# Main_board.net
KiCad netlist of a schematic drawn in EAGLE
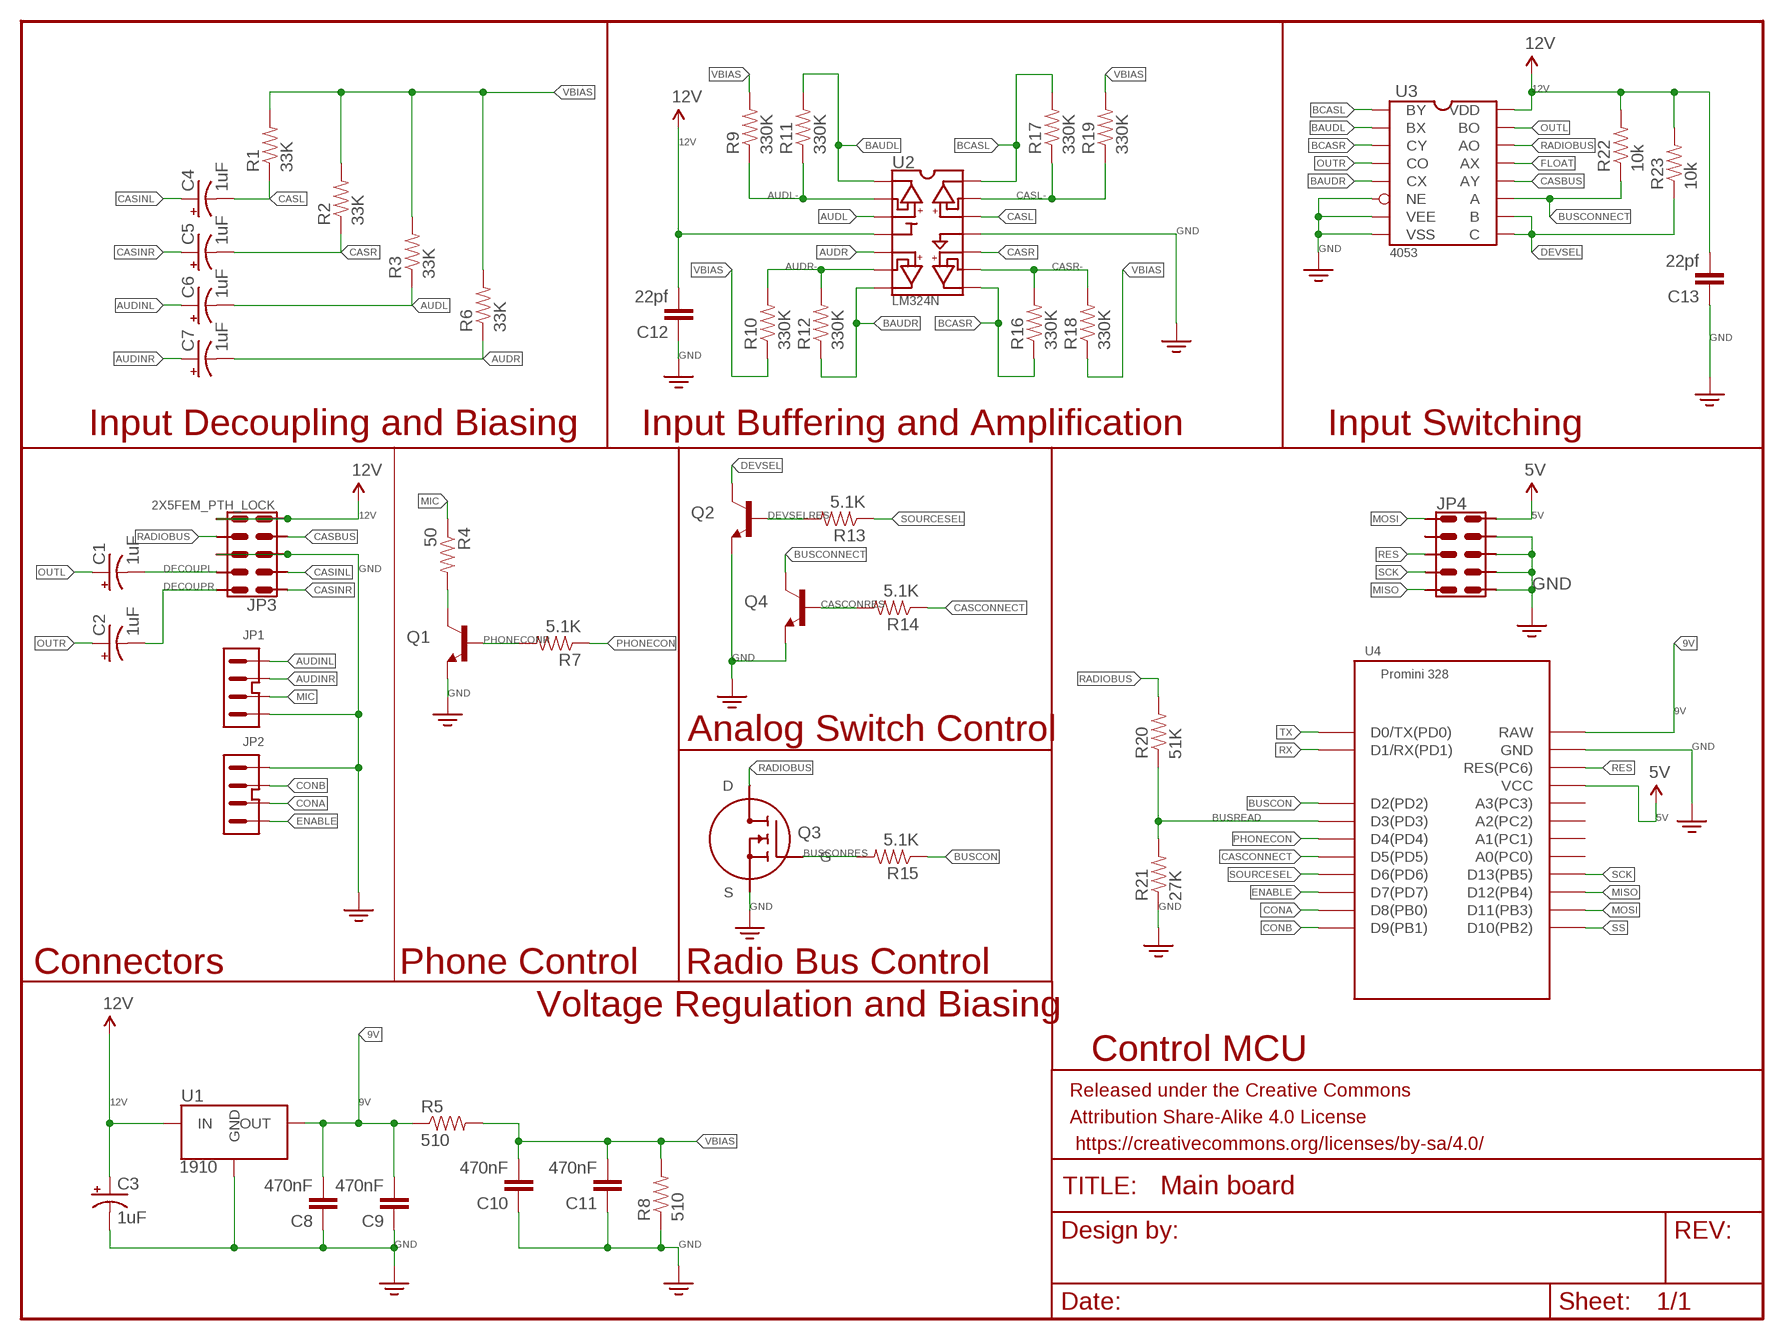
[diagram p0: schematic, sheet 1]

(export (version "E")
  (design (tool "Eeschema 10.0.6"))
  (components
    (comp (ref "C1")
      (value "1uF")
      (footprint "eagle-import:CPOL-RADIAL-10UF-25V")
      (libsource (lib "eagle-import") (part "CAP_POLPTH2"))
    )
    (comp (ref "C2")
      (value "1uF")
      (footprint "eagle-import:CPOL-RADIAL-10UF-25V")
      (libsource (lib "eagle-import") (part "CAP_POLPTH2"))
    )
    (comp (ref "C3")
      (value "1uF")
      (footprint "eagle-import:CPOL-RADIAL-10UF-25V")
      (libsource (lib "eagle-import") (part "CAP_POLPTH2"))
    )
    (comp (ref "C4")
      (value "1uF")
      (footprint "eagle-import:CPOL-RADIAL-10UF-25V")
      (libsource (lib "eagle-import") (part "CAP_POLPTH2"))
    )
    (comp (ref "C5")
      (value "1uF")
      (footprint "eagle-import:CPOL-RADIAL-10UF-25V")
      (libsource (lib "eagle-import") (part "CAP_POLPTH2"))
    )
    (comp (ref "C6")
      (value "1uF")
      (footprint "eagle-import:CPOL-RADIAL-10UF-25V")
      (libsource (lib "eagle-import") (part "CAP_POLPTH2"))
    )
    (comp (ref "C7")
      (value "1uF")
      (footprint "eagle-import:CPOL-RADIAL-10UF-25V")
      (libsource (lib "eagle-import") (part "CAP_POLPTH2"))
    )
    (comp (ref "C8")
      (value "470nF")
      (footprint "eagle-import:0603-CAP")
      (libsource (lib "eagle-import") (part "CAP0603-CAP"))
    )
    (comp (ref "C9")
      (value "470nF")
      (footprint "eagle-import:0603-CAP")
      (libsource (lib "eagle-import") (part "CAP0603-CAP"))
    )
    (comp (ref "C10")
      (value "470nF")
      (footprint "eagle-import:0603-CAP")
      (libsource (lib "eagle-import") (part "CAP0603-CAP"))
    )
    (comp (ref "C11")
      (value "470nF")
      (footprint "eagle-import:0603-CAP")
      (libsource (lib "eagle-import") (part "CAP0603-CAP"))
    )
    (comp (ref "C12")
      (value "22pf")
      (footprint "eagle-import:0603-CAP")
      (libsource (lib "eagle-import") (part "CAP0603-CAP"))
    )
    (comp (ref "C13")
      (value "22pf")
      (footprint "eagle-import:0603-CAP")
      (libsource (lib "eagle-import") (part "CAP0603-CAP"))
    )
    (comp (ref "FRAME1")
      (value "FRAME-LETTERNO_PACKAGE")
      (footprint "eagle-import:DUMMY")
      (fields (field (name "DESIGNER") "Nobody"))
      (libsource (lib "eagle-import") (part "FRAME-LETTERNO_PACKAGE"))
    )
    (comp (ref "JP1")
      (value "4PINJST")
      (footprint "eagle-import:JST-4-PTH-VERT")
      (libsource (lib "eagle-import") (part "4PINJST"))
    )
    (comp (ref "JP2")
      (value "4PINJST")
      (footprint "eagle-import:JST-4-PTH-VERT")
      (libsource (lib "eagle-import") (part "4PINJST"))
    )
    (comp (ref "JP3")
      (value "2X5FEM_PTH_LOCK")
      (footprint "eagle-import:2X5PTHFEMLOCK")
      (libsource (lib "eagle-import") (part "2X5FEM_PTH_LOCK"))
    )
    (comp (ref "JP4")
      (value "2X5FEM_PTH_LOCK")
      (footprint "eagle-import:2X5PTHFEMLOCK")
      (libsource (lib "eagle-import") (part "2X5FEM_PTH_LOCK"))
    )
    (comp (ref "Q1")
      (value "TRANSISTOR_NPNTO-92-AMMO")
      (footprint "eagle-import:TO-92-AMMO")
      (libsource (lib "eagle-import") (part "TRANSISTOR_NPNTO-92-AMMO"))
    )
    (comp (ref "Q2")
      (value "TRANSISTOR_NPNTO-92-AMMO")
      (footprint "eagle-import:TO-92-AMMO")
      (libsource (lib "eagle-import") (part "TRANSISTOR_NPNTO-92-AMMO"))
    )
    (comp (ref "Q3")
      (value "BUZ101S")
      (footprint "eagle-import:TO-220")
      (libsource (lib "eagle-import") (part "BUZ101S"))
    )
    (comp (ref "Q4")
      (value "TRANSISTOR_NPNTO-92-AMMO")
      (footprint "eagle-import:TO-92-AMMO")
      (libsource (lib "eagle-import") (part "TRANSISTOR_NPNTO-92-AMMO"))
    )
    (comp (ref "R1")
      (value "33K")
      (footprint "eagle-import:0603-RES")
      (libsource (lib "eagle-import") (part "RESISTOR0603"))
    )
    (comp (ref "R2")
      (value "33K")
      (footprint "eagle-import:0603-RES")
      (libsource (lib "eagle-import") (part "RESISTOR0603"))
    )
    (comp (ref "R3")
      (value "33K")
      (footprint "eagle-import:0603-RES")
      (libsource (lib "eagle-import") (part "RESISTOR0603"))
    )
    (comp (ref "R4")
      (value "50")
      (footprint "eagle-import:0603-RES")
      (libsource (lib "eagle-import") (part "RESISTOR0603"))
    )
    (comp (ref "R5")
      (value "510")
      (footprint "eagle-import:0603-RES")
      (libsource (lib "eagle-import") (part "RESISTOR0603"))
    )
    (comp (ref "R6")
      (value "33K")
      (footprint "eagle-import:0603-RES")
      (libsource (lib "eagle-import") (part "RESISTOR0603"))
    )
    (comp (ref "R7")
      (value "5.1K")
      (footprint "eagle-import:0603-RES")
      (libsource (lib "eagle-import") (part "RESISTOR0603"))
    )
    (comp (ref "R8")
      (value "510")
      (footprint "eagle-import:0603-RES")
      (libsource (lib "eagle-import") (part "RESISTOR0603"))
    )
    (comp (ref "R9")
      (value "330K")
      (footprint "eagle-import:0603-RES")
      (libsource (lib "eagle-import") (part "RESISTOR0603"))
    )
    (comp (ref "R10")
      (value "330K")
      (footprint "eagle-import:0603-RES")
      (libsource (lib "eagle-import") (part "RESISTOR0603"))
    )
    (comp (ref "R11")
      (value "330K")
      (footprint "eagle-import:0603-RES")
      (libsource (lib "eagle-import") (part "RESISTOR0603"))
    )
    (comp (ref "R12")
      (value "330K")
      (footprint "eagle-import:0603-RES")
      (libsource (lib "eagle-import") (part "RESISTOR0603"))
    )
    (comp (ref "R13")
      (value "5.1K")
      (footprint "eagle-import:0603-RES")
      (libsource (lib "eagle-import") (part "RESISTOR0603"))
    )
    (comp (ref "R14")
      (value "5.1K")
      (footprint "eagle-import:0603-RES")
      (libsource (lib "eagle-import") (part "RESISTOR0603"))
    )
    (comp (ref "R15")
      (value "5.1K")
      (footprint "eagle-import:0603-RES")
      (libsource (lib "eagle-import") (part "RESISTOR0603"))
    )
    (comp (ref "R16")
      (value "330K")
      (footprint "eagle-import:0603-RES")
      (libsource (lib "eagle-import") (part "RESISTOR0603"))
    )
    (comp (ref "R17")
      (value "330K")
      (footprint "eagle-import:0603-RES")
      (libsource (lib "eagle-import") (part "RESISTOR0603"))
    )
    (comp (ref "R18")
      (value "330K")
      (footprint "eagle-import:0603-RES")
      (libsource (lib "eagle-import") (part "RESISTOR0603"))
    )
    (comp (ref "R19")
      (value "330K")
      (footprint "eagle-import:0603-RES")
      (libsource (lib "eagle-import") (part "RESISTOR0603"))
    )
    (comp (ref "R20")
      (value "51K")
      (footprint "eagle-import:0603-RES")
      (libsource (lib "eagle-import") (part "RESISTOR0603"))
    )
    (comp (ref "R21")
      (value "27K")
      (footprint "eagle-import:0603-RES")
      (libsource (lib "eagle-import") (part "RESISTOR0603"))
    )
    (comp (ref "R22")
      (value "10k")
      (footprint "eagle-import:0603-RES")
      (libsource (lib "eagle-import") (part "RESISTOR0603"))
    )
    (comp (ref "R23")
      (value "10k")
      (footprint "eagle-import:0603-RES")
      (libsource (lib "eagle-import") (part "RESISTOR0603"))
    )
    (comp (ref "U1")
      (value "1910")
      (footprint "eagle-import:TO-220")
      (libsource (lib "eagle-import") (part "1910"))
    )
    (comp (ref "U2")
      (value "LM324N")
      (footprint "eagle-import:DIP14")
      (libsource (lib "eagle-import") (part "LM324N"))
    )
    (comp (ref "U3")
      (value "4053")
      (footprint "eagle-import:DIP16")
      (libsource (lib "eagle-import") (part "4053"))
    )
    (comp (ref "U4")
      (value "PROMINIV2NOFTDI")
      (footprint "eagle-import:PROMINIV2NOFTDI")
      (libsource (lib "eagle-import") (part "PROMINIV2NOFTDI"))
    )
  )
  (nets
    (net (code "1") (name "/AUDL-") (class "Default")
      (node (ref "R11") (pin "1") (pinfunction "1_1") (pintype "passive"))
      (node (ref "R9") (pin "1") (pinfunction "1_1") (pintype "passive"))
      (node (ref "U2") (pin "P$2") (pinfunction "A-_P$2") (pintype "bidirectional"))
    )
    (net (code "2") (name "/AUDR-") (class "Default")
      (node (ref "R10") (pin "2") (pinfunction "2_2") (pintype "passive"))
      (node (ref "R12") (pin "2") (pinfunction "2_2") (pintype "passive"))
      (node (ref "U2") (pin "P$6") (pinfunction "B-_P$6") (pintype "bidirectional"))
    )
    (net (code "3") (name "/BUSCONRES") (class "Default")
      (node (ref "Q3") (pin "1") (pinfunction "G_1") (pintype "bidirectional"))
      (node (ref "R15") (pin "2") (pinfunction "2_2") (pintype "passive"))
    )
    (net (code "4") (name "/BUSREAD") (class "Default")
      (node (ref "R20") (pin "1") (pinfunction "1_1") (pintype "passive"))
      (node (ref "R21") (pin "2") (pinfunction "2_2") (pintype "passive"))
      (node (ref "U4") (pin "D3") (pinfunction "D3(PD3)_D3") (pintype "bidirectional"))
    )
    (net (code "5") (name "/CASCONRES") (class "Default")
      (node (ref "Q4") (pin "2") (pinfunction "B_2") (pintype "passive"))
      (node (ref "R14") (pin "2") (pinfunction "2_2") (pintype "passive"))
    )
    (net (code "6") (name "/CASL-") (class "Default")
      (node (ref "R17") (pin "1") (pinfunction "1_1") (pintype "passive"))
      (node (ref "R19") (pin "1") (pinfunction "1_1") (pintype "passive"))
      (node (ref "U2") (pin "P$13") (pinfunction "D-_P$13") (pintype "bidirectional"))
    )
    (net (code "7") (name "/CASR-") (class "Default")
      (node (ref "R16") (pin "2") (pinfunction "2_2") (pintype "passive"))
      (node (ref "R18") (pin "2") (pinfunction "2_2") (pintype "passive"))
      (node (ref "U2") (pin "P$9") (pinfunction "C-_P$9") (pintype "bidirectional"))
    )
    (net (code "8") (name "/DECOUPL") (class "Default")
      (node (ref "C1") (pin "2") (pinfunction "-_2") (pintype "passive"))
      (node (ref "JP3") (pin "P$9") (pinfunction "P$9_P$9") (pintype "bidirectional"))
    )
    (net (code "9") (name "/DECOUPR") (class "Default")
      (node (ref "C2") (pin "2") (pinfunction "-_2") (pintype "passive"))
      (node (ref "JP3") (pin "P$10") (pinfunction "P$10_P$10") (pintype "bidirectional"))
    )
    (net (code "10") (name "/DEVSELRES") (class "Default")
      (node (ref "Q2") (pin "2") (pinfunction "B_2") (pintype "passive"))
      (node (ref "R13") (pin "2") (pinfunction "2_2") (pintype "passive"))
    )
    (net (code "11") (name "/PHONECONR") (class "Default")
      (node (ref "Q1") (pin "2") (pinfunction "B_2") (pintype "passive"))
      (node (ref "R7") (pin "2") (pinfunction "2_2") (pintype "passive"))
    )
    (net (code "12") (name "5V") (class "Default")
      (node (ref "JP4") (pin "P$10") (pinfunction "P$10_P$10") (pintype "bidirectional"))
      (node (ref "U4") (pin "VCC") (pinfunction "VCC_VCC") (pintype "bidirectional"))
    )
    (net (code "13") (name "9V") (class "Default")
      (node (ref "C8") (pin "2") (pinfunction "2_2") (pintype "passive"))
      (node (ref "C9") (pin "2") (pinfunction "2_2") (pintype "passive"))
      (node (ref "R5") (pin "1") (pinfunction "1_1") (pintype "passive"))
      (node (ref "U1") (pin "3") (pinfunction "OUT_3") (pintype "bidirectional"))
      (node (ref "U4") (pin "RAW") (pinfunction "RAW_RAW") (pintype "bidirectional"))
    )
    (net (code "14") (name "12V") (class "Default")
      (node (ref "C12") (pin "2") (pinfunction "2_2") (pintype "passive"))
      (node (ref "C13") (pin "2") (pinfunction "2_2") (pintype "passive"))
      (node (ref "C3") (pin "1") (pinfunction "+_1") (pintype "passive"))
      (node (ref "JP3") (pin "P$5") (pinfunction "P$5_P$5") (pintype "bidirectional"))
      (node (ref "JP3") (pin "P$6") (pinfunction "P$6_P$6") (pintype "bidirectional"))
      (node (ref "R22") (pin "2") (pinfunction "2_2") (pintype "passive"))
      (node (ref "R23") (pin "2") (pinfunction "2_2") (pintype "passive"))
      (node (ref "U1") (pin "1") (pinfunction "IN_1") (pintype "bidirectional"))
      (node (ref "U2") (pin "P$4") (pinfunction "VCC_P$4") (pintype "bidirectional"))
      (node (ref "U3") (pin "P$16") (pinfunction "VDD_P$16") (pintype "bidirectional"))
    )
    (net (code "15") (name "AUDINL") (class "Default")
      (node (ref "C6") (pin "1") (pinfunction "+_1") (pintype "passive"))
      (node (ref "JP1") (pin "1") (pinfunction "P$1_1") (pintype "bidirectional"))
    )
    (net (code "16") (name "AUDINR") (class "Default")
      (node (ref "C7") (pin "1") (pinfunction "+_1") (pintype "passive"))
      (node (ref "JP1") (pin "2") (pinfunction "P$2_2") (pintype "bidirectional"))
    )
    (net (code "17") (name "AUDL") (class "Default")
      (node (ref "C6") (pin "2") (pinfunction "-_2") (pintype "passive"))
      (node (ref "R3") (pin "1") (pinfunction "1_1") (pintype "passive"))
      (node (ref "U2") (pin "P$3") (pinfunction "A+_P$3") (pintype "bidirectional"))
    )
    (net (code "18") (name "AUDR") (class "Default")
      (node (ref "C7") (pin "2") (pinfunction "-_2") (pintype "passive"))
      (node (ref "R6") (pin "1") (pinfunction "1_1") (pintype "passive"))
      (node (ref "U2") (pin "P$5") (pinfunction "B+_P$5") (pintype "bidirectional"))
    )
    (net (code "19") (name "BAUDL") (class "Default")
      (node (ref "R11") (pin "2") (pinfunction "2_2") (pintype "passive"))
      (node (ref "U2") (pin "P$1") (pinfunction "AO_P$1") (pintype "bidirectional"))
      (node (ref "U3") (pin "P$2") (pinfunction "BX_P$2") (pintype "bidirectional"))
    )
    (net (code "20") (name "BAUDR") (class "Default")
      (node (ref "R12") (pin "1") (pinfunction "1_1") (pintype "passive"))
      (node (ref "U2") (pin "P$7") (pinfunction "BO_P$7") (pintype "bidirectional"))
      (node (ref "U3") (pin "P$5") (pinfunction "CX_P$5") (pintype "bidirectional"))
    )
    (net (code "21") (name "BCASL") (class "Default")
      (node (ref "R17") (pin "2") (pinfunction "2_2") (pintype "passive"))
      (node (ref "U2") (pin "P$14") (pinfunction "DO_P$14") (pintype "bidirectional"))
      (node (ref "U3") (pin "P$1") (pinfunction "BY_P$1") (pintype "bidirectional"))
    )
    (net (code "22") (name "BCASR") (class "Default")
      (node (ref "R16") (pin "1") (pinfunction "1_1") (pintype "passive"))
      (node (ref "U2") (pin "P$8") (pinfunction "CO_P$8") (pintype "bidirectional"))
      (node (ref "U3") (pin "P$3") (pinfunction "CY_P$3") (pintype "bidirectional"))
    )
    (net (code "23") (name "BUSCON") (class "Default")
      (node (ref "R15") (pin "1") (pinfunction "1_1") (pintype "passive"))
      (node (ref "U4") (pin "D2") (pinfunction "D2(PD2)_D2") (pintype "bidirectional"))
    )
    (net (code "24") (name "BUSCONNECT") (class "Default")
      (node (ref "Q4") (pin "3") (pinfunction "C_3") (pintype "passive"))
      (node (ref "R22") (pin "1") (pinfunction "1_1") (pintype "passive"))
      (node (ref "U3") (pin "P$11") (pinfunction "A_P$11") (pintype "bidirectional"))
    )
    (net (code "25") (name "CASBUS") (class "Default")
      (node (ref "JP3") (pin "P$4") (pinfunction "P$4_P$4") (pintype "bidirectional"))
      (node (ref "U3") (pin "P$12") (pinfunction "AY_P$12") (pintype "bidirectional"))
    )
    (net (code "26") (name "CASCONNECT") (class "Default")
      (node (ref "R14") (pin "1") (pinfunction "1_1") (pintype "passive"))
      (node (ref "U4") (pin "D5") (pinfunction "D5(PD5)_D5") (pintype "bidirectional"))
    )
    (net (code "27") (name "CASINL") (class "Default")
      (node (ref "C4") (pin "1") (pinfunction "+_1") (pintype "passive"))
      (node (ref "JP3") (pin "P$2") (pinfunction "P$2_P$2") (pintype "bidirectional"))
    )
    (net (code "28") (name "CASINR") (class "Default")
      (node (ref "C5") (pin "1") (pinfunction "+_1") (pintype "passive"))
      (node (ref "JP3") (pin "P$1") (pinfunction "P$1_P$1") (pintype "bidirectional"))
    )
    (net (code "29") (name "CASL") (class "Default")
      (node (ref "C4") (pin "2") (pinfunction "-_2") (pintype "passive"))
      (node (ref "R1") (pin "1") (pinfunction "1_1") (pintype "passive"))
      (node (ref "U2") (pin "P$12") (pinfunction "D+_P$12") (pintype "bidirectional"))
    )
    (net (code "30") (name "CASR") (class "Default")
      (node (ref "C5") (pin "2") (pinfunction "-_2") (pintype "passive"))
      (node (ref "R2") (pin "1") (pinfunction "1_1") (pintype "passive"))
      (node (ref "U2") (pin "P$10") (pinfunction "C+_P$10") (pintype "bidirectional"))
    )
    (net (code "31") (name "CONA") (class "Default")
      (node (ref "JP2") (pin "3") (pinfunction "P$3_3") (pintype "bidirectional"))
      (node (ref "U4") (pin "D8") (pinfunction "D8(PB0)_D8") (pintype "bidirectional"))
    )
    (net (code "32") (name "CONB") (class "Default")
      (node (ref "JP2") (pin "2") (pinfunction "P$2_2") (pintype "bidirectional"))
      (node (ref "U4") (pin "D9") (pinfunction "D9(PB1)_D9") (pintype "bidirectional"))
    )
    (net (code "33") (name "DEVSEL") (class "Default")
      (node (ref "Q2") (pin "3") (pinfunction "C_3") (pintype "passive"))
      (node (ref "R23") (pin "1") (pinfunction "1_1") (pintype "passive"))
      (node (ref "U3") (pin "P$10") (pinfunction "B_P$10") (pintype "bidirectional"))
      (node (ref "U3") (pin "P$9") (pinfunction "C_P$9") (pintype "bidirectional"))
    )
    (net (code "34") (name "ENABLE") (class "Default")
      (node (ref "JP2") (pin "4") (pinfunction "P$4_4") (pintype "bidirectional"))
      (node (ref "U4") (pin "D7") (pinfunction "D7(PD7)_D7") (pintype "bidirectional"))
    )
    (net (code "35") (name "FLOAT") (class "Default")
      (node (ref "U3") (pin "P$13") (pinfunction "AX_P$13") (pintype "bidirectional"))
    )
    (net (code "36") (name "GND2") (class "Default")
      (node (ref "C10") (pin "1") (pinfunction "1_1") (pintype "passive"))
      (node (ref "C11") (pin "1") (pinfunction "1_1") (pintype "passive"))
      (node (ref "C12") (pin "1") (pinfunction "1_1") (pintype "passive"))
      (node (ref "C13") (pin "1") (pinfunction "1_1") (pintype "passive"))
      (node (ref "C3") (pin "2") (pinfunction "-_2") (pintype "passive"))
      (node (ref "C8") (pin "1") (pinfunction "1_1") (pintype "passive"))
      (node (ref "C9") (pin "1") (pinfunction "1_1") (pintype "passive"))
      (node (ref "JP1") (pin "4") (pinfunction "P$4_4") (pintype "bidirectional"))
      (node (ref "JP2") (pin "1") (pinfunction "P$1_1") (pintype "bidirectional"))
      (node (ref "JP3") (pin "P$3") (pinfunction "P$3_P$3") (pintype "bidirectional"))
      (node (ref "JP3") (pin "P$8") (pinfunction "P$8_P$8") (pintype "bidirectional"))
      (node (ref "JP4") (pin "P$6") (pinfunction "P$6_P$6") (pintype "bidirectional"))
      (node (ref "JP4") (pin "P$7") (pinfunction "P$7_P$7") (pintype "bidirectional"))
      (node (ref "JP4") (pin "P$8") (pinfunction "P$8_P$8") (pintype "bidirectional"))
      (node (ref "JP4") (pin "P$9") (pinfunction "P$9_P$9") (pintype "bidirectional"))
      (node (ref "Q1") (pin "1") (pinfunction "E_1") (pintype "passive"))
      (node (ref "Q2") (pin "1") (pinfunction "E_1") (pintype "passive"))
      (node (ref "Q3") (pin "3") (pinfunction "S_3") (pintype "bidirectional"))
      (node (ref "Q4") (pin "1") (pinfunction "E_1") (pintype "passive"))
      (node (ref "R21") (pin "1") (pinfunction "1_1") (pintype "passive"))
      (node (ref "R8") (pin "1") (pinfunction "1_1") (pintype "passive"))
      (node (ref "U1") (pin "2") (pinfunction "GND_2") (pintype "bidirectional"))
      (node (ref "U2") (pin "P$11") (pinfunction "GND_P$11") (pintype "bidirectional"))
      (node (ref "U3") (pin "P$6") (pinfunction "NE_P$6") (pintype "bidirectional"))
      (node (ref "U3") (pin "P$7") (pinfunction "VEE_P$7") (pintype "bidirectional"))
      (node (ref "U3") (pin "P$8") (pinfunction "VSS_P$8") (pintype "bidirectional"))
      (node (ref "U4") (pin "GND1") (pinfunction "GND_GND1") (pintype "bidirectional"))
      (node (ref "U4") (pin "GND3") (pinfunction "GND_GND3") (pintype "bidirectional"))
    )
    (net (code "37") (name "MIC") (class "Default")
      (node (ref "JP1") (pin "3") (pinfunction "P$3_3") (pintype "bidirectional"))
      (node (ref "R4") (pin "1") (pinfunction "1_1") (pintype "passive"))
    )
    (net (code "38") (name "MISO") (class "Default")
      (node (ref "JP4") (pin "P$5") (pinfunction "P$5_P$5") (pintype "bidirectional"))
      (node (ref "U4") (pin "D12") (pinfunction "D12(PB4)_D12") (pintype "bidirectional"))
    )
    (net (code "39") (name "MOSI") (class "Default")
      (node (ref "JP4") (pin "P$1") (pinfunction "P$1_P$1") (pintype "bidirectional"))
      (node (ref "U4") (pin "D11") (pinfunction "D11(PB3)_D11") (pintype "bidirectional"))
    )
    (net (code "40") (name "Net-(Q1-C)") (class "Default")
      (node (ref "Q1") (pin "3") (pinfunction "C_3") (pintype "passive"))
      (node (ref "R4") (pin "2") (pinfunction "2_2") (pintype "passive"))
    )
    (net (code "41") (name "OUTL") (class "Default")
      (node (ref "C1") (pin "1") (pinfunction "+_1") (pintype "passive"))
      (node (ref "U3") (pin "P$15") (pinfunction "BO_P$15") (pintype "bidirectional"))
    )
    (net (code "42") (name "OUTR") (class "Default")
      (node (ref "C2") (pin "1") (pinfunction "+_1") (pintype "passive"))
      (node (ref "U3") (pin "P$4") (pinfunction "CO_P$4") (pintype "bidirectional"))
    )
    (net (code "43") (name "PHONECON") (class "Default")
      (node (ref "R7") (pin "1") (pinfunction "1_1") (pintype "passive"))
      (node (ref "U4") (pin "D4") (pinfunction "D4(PD4)_D4") (pintype "bidirectional"))
    )
    (net (code "44") (name "RADIOBUS") (class "Default")
      (node (ref "JP3") (pin "P$7") (pinfunction "P$7_P$7") (pintype "bidirectional"))
      (node (ref "Q3") (pin "2") (pinfunction "D_2") (pintype "bidirectional"))
      (node (ref "R20") (pin "2") (pinfunction "2_2") (pintype "passive"))
      (node (ref "U3") (pin "P$14") (pinfunction "AO_P$14") (pintype "bidirectional"))
    )
    (net (code "45") (name "RES") (class "Default")
      (node (ref "JP4") (pin "P$3") (pinfunction "P$3_P$3") (pintype "bidirectional"))
      (node (ref "U4") (pin "RES1") (pinfunction "RES(PC6)_RES1") (pintype "bidirectional"))
      (node (ref "U4") (pin "RES3") (pinfunction "RES(PC6)_RES3") (pintype "bidirectional"))
    )
    (net (code "46") (name "RX") (class "Default")
      (node (ref "U4") (pin "D1") (pinfunction "D1/RX(PD1)_D1") (pintype "bidirectional"))
    )
    (net (code "47") (name "SCK") (class "Default")
      (node (ref "JP4") (pin "P$4") (pinfunction "P$4_P$4") (pintype "bidirectional"))
      (node (ref "U4") (pin "D13") (pinfunction "D13(PB5)_D13") (pintype "bidirectional"))
    )
    (net (code "48") (name "SOURCESEL") (class "Default")
      (node (ref "R13") (pin "1") (pinfunction "1_1") (pintype "passive"))
      (node (ref "U4") (pin "D6") (pinfunction "D6(PD6)_D6") (pintype "bidirectional"))
    )
    (net (code "49") (name "SS") (class "Default")
      (node (ref "U4") (pin "D10") (pinfunction "D10(PB2)_D10") (pintype "bidirectional"))
    )
    (net (code "50") (name "TX") (class "Default")
      (node (ref "U4") (pin "D0") (pinfunction "D0/TX(PD0)_D0") (pintype "bidirectional"))
    )
    (net (code "51") (name "VBIAS") (class "Default")
      (node (ref "C10") (pin "2") (pinfunction "2_2") (pintype "passive"))
      (node (ref "C11") (pin "2") (pinfunction "2_2") (pintype "passive"))
      (node (ref "R1") (pin "2") (pinfunction "2_2") (pintype "passive"))
      (node (ref "R10") (pin "1") (pinfunction "1_1") (pintype "passive"))
      (node (ref "R18") (pin "1") (pinfunction "1_1") (pintype "passive"))
      (node (ref "R19") (pin "2") (pinfunction "2_2") (pintype "passive"))
      (node (ref "R2") (pin "2") (pinfunction "2_2") (pintype "passive"))
      (node (ref "R3") (pin "2") (pinfunction "2_2") (pintype "passive"))
      (node (ref "R5") (pin "2") (pinfunction "2_2") (pintype "passive"))
      (node (ref "R6") (pin "2") (pinfunction "2_2") (pintype "passive"))
      (node (ref "R8") (pin "2") (pinfunction "2_2") (pintype "passive"))
      (node (ref "R9") (pin "2") (pinfunction "2_2") (pintype "passive"))
    )
    (net (code "52") (name "unconnected-(JP4-PadP$2)") (class "Default")
      (node (ref "JP4") (pin "P$2") (pinfunction "P$2_P$2") (pintype "bidirectional"))
    )
    (net (code "53") (name "unconnected-(U4-A0(PC0)-PadA0)") (class "Default")
      (node (ref "U4") (pin "A0") (pinfunction "A0(PC0)_A0") (pintype "bidirectional"))
    )
    (net (code "54") (name "unconnected-(U4-A1(PC1)-PadA1)") (class "Default")
      (node (ref "U4") (pin "A1") (pinfunction "A1(PC1)_A1") (pintype "bidirectional"))
    )
    (net (code "55") (name "unconnected-(U4-A2(PC2)-PadA2)") (class "Default")
      (node (ref "U4") (pin "A2") (pinfunction "A2(PC2)_A2") (pintype "bidirectional"))
    )
    (net (code "56") (name "unconnected-(U4-A3(PC3)-PadA3)") (class "Default")
      (node (ref "U4") (pin "A3") (pinfunction "A3(PC3)_A3") (pintype "bidirectional"))
    )
  )
)
